# HX711_2.net
KiCad netlist of a schematic drawn in Altium Designer
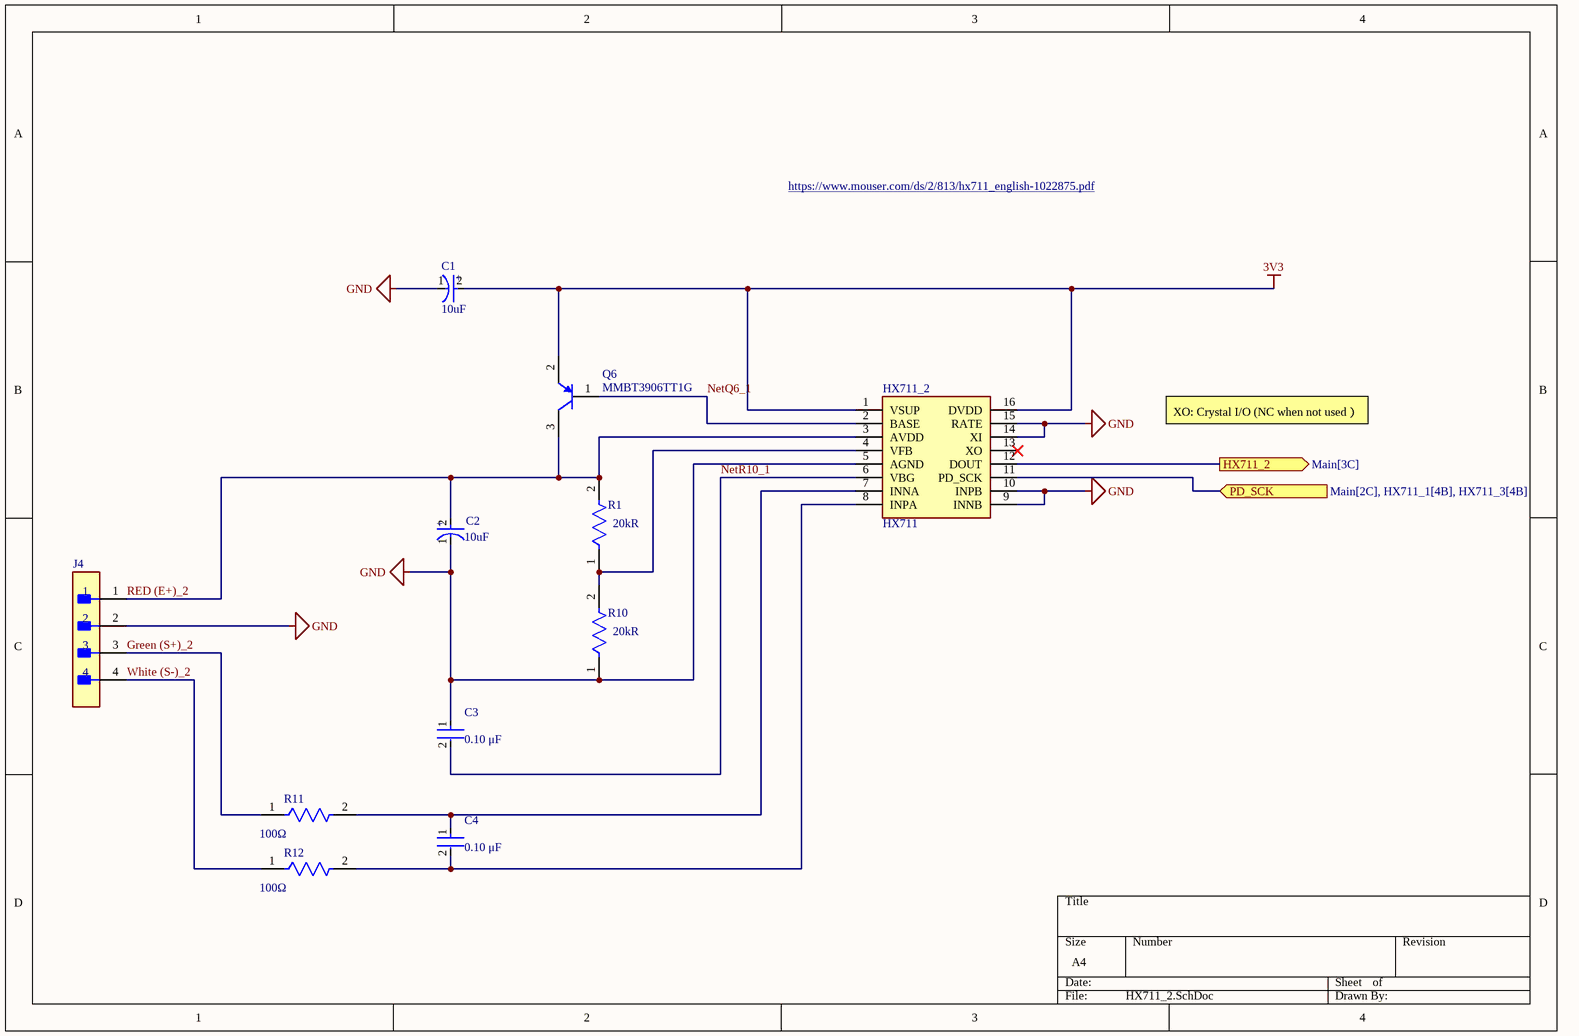
[diagram p0: HX711_2.SchDoc]

(export (version "E")
  (design (tool "Eeschema 10.0.6"))
  (components
    (comp (ref "C1")
      (value "EDK106M035A9BAA")
      (footprint "FP-EDK9B-MFG")
      (description "CAP ALUM 10UF 20% 35V SMD")
      (fields
        (field (name "CAPACITANCE") "10uF")
        (field (name "MANUFACTURER") "Kemet")
        (field (name "OCTOPART") "https://octopart.com/edk106m035a9baa-kemet-26722193")
      )
      (libsource (lib "Altium Content Vault") (part "cf48714ba7e38822c1575c7ec0b6d1f"))
    )
    (comp (ref "C2")
      (value "EDK106M035A9BAA")
      (footprint "FP-EDK9B-MFG")
      (description "CAP ALUM 10UF 20% 35V SMD")
      (fields
        (field (name "CAPACITANCE") "10uF")
        (field (name "MANUFACTURER") "Kemet")
        (field (name "OCTOPART") "https://octopart.com/edk106m035a9baa-kemet-26722193")
      )
      (libsource (lib "Altium Content Vault") (part "cf48714ba7e38822c1575c7ec0b6d1f"))
    )
    (comp (ref "C3")
      (value "0.10 μF")
      (footprint "FP-C0603C-CF-MFG")
      (description "CAP CER 0.1UF 25V X7R 0603")
      (fields
        (field (name "OCTOPART") "https://octopart.com/c0603c104k3rac7411-kemet-9138804")
        (field (name "MANUFACTURER") "KEMET")
      )
      (libsource (lib "Altium Content Vault") (part "b4654b650e69147ec39a6b967a45e02"))
    )
    (comp (ref "C4")
      (value "0.10 μF")
      (footprint "FP-C0603C-CF-MFG")
      (description "CAP CER 0.1UF 25V X7R 0603")
      (fields
        (field (name "OCTOPART") "https://octopart.com/c0603c104k3rac7411-kemet-9138804")
        (field (name "MANUFACTURER") "KEMET")
      )
      (libsource (lib "Altium Content Vault") (part "b4654b650e69147ec39a6b967a45e02"))
    )
    (comp (ref "HX711_2")
      (value "HX711")
      (footprint "SamacSys:SOIC127P600X160-16N")
      (description "Integrated Circuit")
      (libsource (lib "*") (part "HX711"))
    )
    (comp (ref "J4")
      (value "TSW-104-23-T-S")
      (footprint "FP-TSW-104-23-T-S-MFG")
      (description "CONN HEADER VERT 4POS 2.54MM")
      (libsource (lib "Altium Content Vault") (part "f33e0d423099bbb9e64512431cdbdf7"))
    )
    (comp (ref "Q6")
      (value "MMBT3906TT1G")
      (footprint "ONSC-SC-75-3-463-01_V")
      (description "General Purpose Transistor, PNP Silicon, 3-Pin SC-75, Pb-Free, Tape and Reel")
      (fields (field (name "MANUFACTURER") "On Semiconductor"))
      (libsource (lib "Altium Content Vault") (part "ONSC-PNP-B1E2C3-3"))
    )
    (comp (ref "R1")
      (value "CRCW060320K0FKEAHP")
      (footprint "FP-CRCW0603-HPe3-MFG")
      (description "RES Thick Film, 20kΩ, 1%, 0.33W, 100ppm/°C, 0603")
      (fields (field (name "RESISTANCE") "20kR") (field (name "TOLERANCE") "1%"))
      (libsource (lib "Altium Content Vault") (part "1029c3af85768c4190bb7ad29bc67b5"))
    )
    (comp (ref "R10")
      (value "CRCW060320K0FKEAHP")
      (footprint "FP-CRCW0603-HPe3-MFG")
      (description "RES Thick Film, 20kΩ, 1%, 0.33W, 100ppm/°C, 0603")
      (fields (field (name "RESISTANCE") "20kR") (field (name "TOLERANCE") "1%"))
      (libsource (lib "Altium Content Vault") (part "1029c3af85768c4190bb7ad29bc67b5"))
    )
    (comp (ref "R11")
      (value "100Ω")
      (footprint "FP-RT0603-MFG")
      (description "RES SMD 100 OHM 1% 1/10W 0603")
      (fields
        (field (name "MANUFACTURER PART NUMBER") "RT0603FRE07100RL")
        (field (name "MANUFACTURER") "Yageo")
      )
      (libsource (lib "Altium Content Vault") (part "1029c3af85768c4190bb7ad29bc67b5"))
    )
    (comp (ref "R12")
      (value "100Ω")
      (footprint "FP-RT0603-MFG")
      (description "RES SMD 100 OHM 1% 1/10W 0603")
      (fields
        (field (name "MANUFACTURER PART NUMBER") "RT0603FRE07100RL")
        (field (name "MANUFACTURER") "Yageo")
      )
      (libsource (lib "Altium Content Vault") (part "1029c3af85768c4190bb7ad29bc67b5"))
    )
  )
  (nets
    (net (code "1") (name "/Green (S+)_2") (class "Default")
      (node (ref "J4") (pin "3") (pinfunction "3_3") (pintype "passive"))
      (node (ref "R11") (pin "1") (pinfunction "1_1") (pintype "passive"))
    )
    (net (code "2") (name "/HX711_2") (class "Default")
      (node (ref "HX711_2") (pin "12") (pinfunction "DOUT_12") (pintype "passive"))
    )
    (net (code "3") (name "/NetQ6_1") (class "Default")
      (node (ref "HX711_2") (pin "2") (pinfunction "BASE_2") (pintype "passive"))
      (node (ref "Q6") (pin "1") (pinfunction "B_1") (pintype "passive"))
    )
    (net (code "4") (name "/NetR10_1") (class "Default")
      (node (ref "C3") (pin "2") (pinfunction "2_2") (pintype "passive"))
      (node (ref "HX711_2") (pin "6") (pinfunction "VBG_6") (pintype "passive"))
    )
    (net (code "5") (name "/PD_SCK") (class "Default")
      (node (ref "HX711_2") (pin "11") (pinfunction "PD_SCK_11") (pintype "passive"))
    )
    (net (code "6") (name "/RED (E+)_2") (class "Default")
      (node (ref "C2") (pin "2") (pinfunction "A_2") (pintype "passive"))
      (node (ref "HX711_2") (pin "3") (pinfunction "AVDD_3") (pintype "passive"))
      (node (ref "J4") (pin "1") (pinfunction "1_1") (pintype "passive"))
      (node (ref "Q6") (pin "3") (pinfunction "C_3") (pintype "passive"))
      (node (ref "R1") (pin "2") (pinfunction "2_2") (pintype "passive"))
    )
    (net (code "7") (name "/White (S-)_2") (class "Default")
      (node (ref "J4") (pin "4") (pinfunction "4_4") (pintype "passive"))
      (node (ref "R12") (pin "1") (pinfunction "1_1") (pintype "passive"))
    )
    (net (code "8") (name "3V3") (class "Default")
      (node (ref "C1") (pin "2") (pinfunction "A_2") (pintype "passive"))
      (node (ref "HX711_2") (pin "1") (pinfunction "VSUP_1") (pintype "passive"))
      (node (ref "HX711_2") (pin "16") (pinfunction "DVDD_16") (pintype "passive"))
      (node (ref "Q6") (pin "2") (pinfunction "E_2") (pintype "passive"))
    )
    (net (code "9") (name "GND") (class "Default")
      (node (ref "C1") (pin "1") (pinfunction "C_1") (pintype "passive"))
      (node (ref "C2") (pin "1") (pinfunction "C_1") (pintype "passive"))
      (node (ref "C3") (pin "1") (pinfunction "1_1") (pintype "passive"))
      (node (ref "HX711_2") (pin "10") (pinfunction "INPB_10") (pintype "passive"))
      (node (ref "HX711_2") (pin "14") (pinfunction "XI_14") (pintype "passive"))
      (node (ref "HX711_2") (pin "15") (pinfunction "RATE_15") (pintype "passive"))
      (node (ref "HX711_2") (pin "5") (pinfunction "AGND_5") (pintype "passive"))
      (node (ref "HX711_2") (pin "9") (pinfunction "INNB_9") (pintype "passive"))
      (node (ref "J4") (pin "2") (pinfunction "2_2") (pintype "passive"))
      (node (ref "R10") (pin "1") (pinfunction "1_1") (pintype "passive"))
    )
    (net (code "10") (name "Net-(HX711_2-INNA)") (class "Default")
      (node (ref "C4") (pin "1") (pinfunction "1_1") (pintype "passive"))
      (node (ref "HX711_2") (pin "7") (pinfunction "INNA_7") (pintype "passive"))
      (node (ref "R11") (pin "2") (pinfunction "2_2") (pintype "passive"))
    )
    (net (code "11") (name "Net-(HX711_2-INPA)") (class "Default")
      (node (ref "C4") (pin "2") (pinfunction "2_2") (pintype "passive"))
      (node (ref "HX711_2") (pin "8") (pinfunction "INPA_8") (pintype "passive"))
      (node (ref "R12") (pin "2") (pinfunction "2_2") (pintype "passive"))
    )
    (net (code "12") (name "Net-(HX711_2-VFB)") (class "Default")
      (node (ref "HX711_2") (pin "4") (pinfunction "VFB_4") (pintype "passive"))
      (node (ref "R1") (pin "1") (pinfunction "1_1") (pintype "passive"))
      (node (ref "R10") (pin "2") (pinfunction "2_2") (pintype "passive"))
    )
    (net (code "13") (name "unconnected-(HX711_2-XO-Pad13)") (class "Default")
      (node (ref "HX711_2") (pin "13") (pinfunction "XO_13") (pintype "passive+no_connect"))
    )
  )
)
